# MCU.net
KiCad netlist of a schematic drawn in Altium Designer
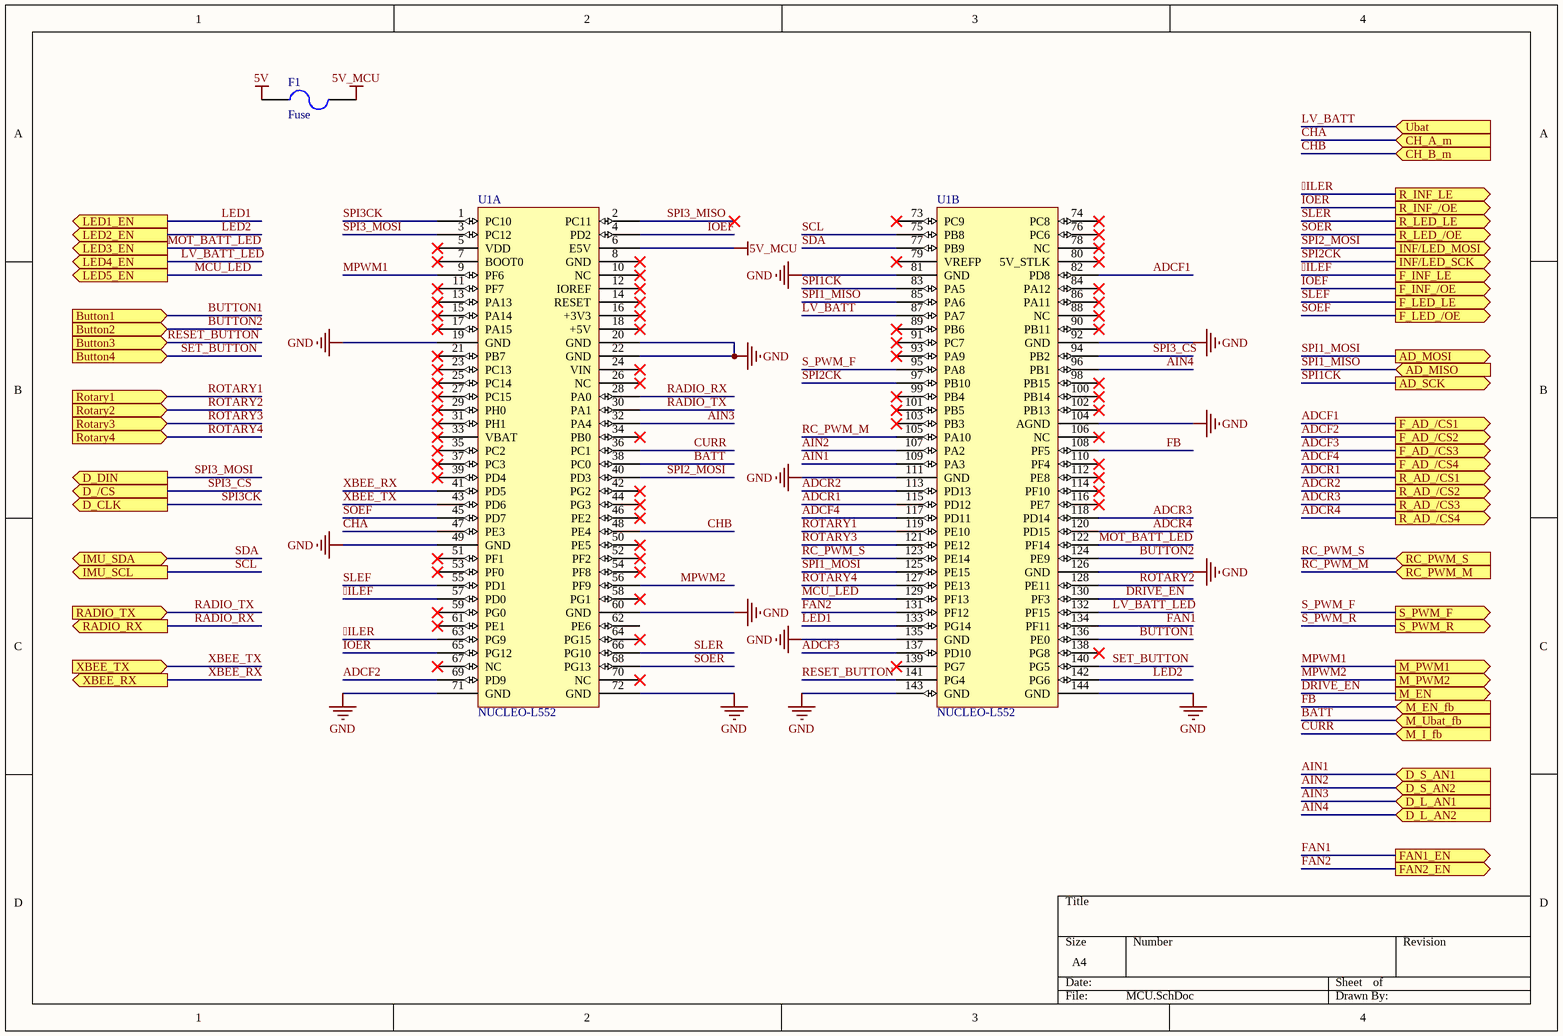
[diagram p0: MCU.SchDoc]

(export (version "E")
  (design (tool "Eeschema 10.0.6"))
  (components
    (comp (ref "F1")
      (value "Fuse")
      (footprint "F_0603")
      (fields (field (name "PART NUMBER") "MC06CF.500") (field (name "NI PART NUMBER") "766324-01"))
      (libsource (lib "Components") (part "Fuse"))
    )
    (comp (ref "U1")
      (value "NUCLEO-L552")
      (footprint "FP_NUCLEO-144")
      (libsource (lib "hallglib") (part "NUCLEO-L552"))
    )
  )
  (nets
    (net (code "1") (name "/ILEF") (class "Default")
      (node (ref "U1") (pin "57") (pinfunction "PD0_57") (pintype "bidirectional"))
    )
    (net (code "2") (name "/ILER") (class "Default")
      (node (ref "U1") (pin "63") (pinfunction "PG9_63") (pintype "bidirectional"))
    )
    (net (code "3") (name "/ADCF1") (class "Default")
      (node (ref "U1") (pin "82") (pinfunction "PD8_82") (pintype "bidirectional"))
    )
    (net (code "4") (name "/ADCF2") (class "Default")
      (node (ref "U1") (pin "69") (pinfunction "PD9_69") (pintype "bidirectional"))
    )
    (net (code "5") (name "/ADCF3") (class "Default")
      (node (ref "U1") (pin "137") (pinfunction "PD10_137") (pintype "bidirectional"))
    )
    (net (code "6") (name "/ADCF4") (class "Default")
      (node (ref "U1") (pin "117") (pinfunction "PD11_117") (pintype "bidirectional"))
    )
    (net (code "7") (name "/ADCR1") (class "Default")
      (node (ref "U1") (pin "115") (pinfunction "PD12_115") (pintype "bidirectional"))
    )
    (net (code "8") (name "/ADCR2") (class "Default")
      (node (ref "U1") (pin "113") (pinfunction "PD13_113") (pintype "bidirectional"))
    )
    (net (code "9") (name "/ADCR3") (class "Default")
      (node (ref "U1") (pin "118") (pinfunction "PD14_118") (pintype "bidirectional"))
    )
    (net (code "10") (name "/ADCR4") (class "Default")
      (node (ref "U1") (pin "120") (pinfunction "PD15_120") (pintype "bidirectional"))
    )
    (net (code "11") (name "/AIN1") (class "Default")
      (node (ref "U1") (pin "109") (pinfunction "PA3_109") (pintype "bidirectional"))
    )
    (net (code "12") (name "/AIN2") (class "Default")
      (node (ref "U1") (pin "107") (pinfunction "PA2_107") (pintype "bidirectional"))
    )
    (net (code "13") (name "/AIN3") (class "Default")
      (node (ref "U1") (pin "32") (pinfunction "PA4_32") (pintype "bidirectional"))
    )
    (net (code "14") (name "/AIN4") (class "Default")
      (node (ref "U1") (pin "96") (pinfunction "PB1_96") (pintype "bidirectional"))
    )
    (net (code "15") (name "/BATT") (class "Default")
      (node (ref "U1") (pin "38") (pinfunction "PC0_38") (pintype "bidirectional"))
    )
    (net (code "16") (name "/BUTTON1") (class "Default")
      (node (ref "U1") (pin "136") (pinfunction "PE0_136") (pintype "bidirectional"))
    )
    (net (code "17") (name "/BUTTON2") (class "Default")
      (node (ref "U1") (pin "124") (pinfunction "PE9_124") (pintype "bidirectional"))
    )
    (net (code "18") (name "/CHA") (class "Default")
      (node (ref "U1") (pin "47") (pinfunction "PE3_47") (pintype "bidirectional"))
    )
    (net (code "19") (name "/CHB") (class "Default")
      (node (ref "U1") (pin "48") (pinfunction "PE4_48") (pintype "bidirectional"))
    )
    (net (code "20") (name "/CURR") (class "Default")
      (node (ref "U1") (pin "36") (pinfunction "PC1_36") (pintype "bidirectional"))
    )
    (net (code "21") (name "/DRIVE_EN") (class "Default")
      (node (ref "U1") (pin "130") (pinfunction "PF3_130") (pintype "bidirectional"))
    )
    (net (code "22") (name "/FAN1") (class "Default")
      (node (ref "U1") (pin "134") (pinfunction "PF11_134") (pintype "bidirectional"))
    )
    (net (code "23") (name "/FAN2") (class "Default")
      (node (ref "U1") (pin "131") (pinfunction "PF12_131") (pintype "bidirectional"))
    )
    (net (code "24") (name "/FB") (class "Default")
      (node (ref "U1") (pin "108") (pinfunction "PF5_108") (pintype "bidirectional"))
    )
    (net (code "25") (name "/IOEF") (class "Default")
      (node (ref "U1") (pin "4") (pinfunction "PD2_4") (pintype "bidirectional"))
    )
    (net (code "26") (name "/IOER") (class "Default")
      (node (ref "U1") (pin "65") (pinfunction "PG12_65") (pintype "bidirectional"))
    )
    (net (code "27") (name "/LED1") (class "Default")
      (node (ref "U1") (pin "133") (pinfunction "PG14_133") (pintype "bidirectional"))
    )
    (net (code "28") (name "/LED2") (class "Default")
      (node (ref "U1") (pin "142") (pinfunction "PG6_142") (pintype "bidirectional"))
    )
    (net (code "29") (name "/LV_BATT") (class "Default")
      (node (ref "U1") (pin "87") (pinfunction "PA7_87") (pintype "bidirectional"))
    )
    (net (code "30") (name "/LV_BATT_LED") (class "Default")
      (node (ref "U1") (pin "132") (pinfunction "PF15_132") (pintype "bidirectional"))
    )
    (net (code "31") (name "/MCU_LED") (class "Default")
      (node (ref "U1") (pin "129") (pinfunction "PF13_129") (pintype "bidirectional"))
    )
    (net (code "32") (name "/MOT_BATT_LED") (class "Default")
      (node (ref "U1") (pin "122") (pinfunction "PF14_122") (pintype "bidirectional"))
    )
    (net (code "33") (name "/MPWM1") (class "Default")
      (node (ref "U1") (pin "9") (pinfunction "PF6_9") (pintype "bidirectional"))
    )
    (net (code "34") (name "/MPWM2") (class "Default")
      (node (ref "U1") (pin "56") (pinfunction "PF9_56") (pintype "bidirectional"))
    )
    (net (code "35") (name "/RADIO_RX") (class "Default")
      (node (ref "U1") (pin "28") (pinfunction "PA0_28") (pintype "bidirectional"))
    )
    (net (code "36") (name "/RADIO_TX") (class "Default")
      (node (ref "U1") (pin "30") (pinfunction "PA1_30") (pintype "bidirectional"))
    )
    (net (code "37") (name "/RC_PWM_M") (class "Default")
      (node (ref "U1") (pin "105") (pinfunction "PA10_105") (pintype "bidirectional"))
    )
    (net (code "38") (name "/RC_PWM_S") (class "Default")
      (node (ref "U1") (pin "123") (pinfunction "PE14_123") (pintype "bidirectional"))
    )
    (net (code "39") (name "/RESET_BUTTON") (class "Default")
      (node (ref "U1") (pin "141") (pinfunction "PG4_141") (pintype "power_in"))
    )
    (net (code "40") (name "/ROTARY1") (class "Default")
      (node (ref "U1") (pin "119") (pinfunction "PE10_119") (pintype "bidirectional"))
    )
    (net (code "41") (name "/ROTARY2") (class "Default")
      (node (ref "U1") (pin "128") (pinfunction "PE11_128") (pintype "bidirectional"))
    )
    (net (code "42") (name "/ROTARY3") (class "Default")
      (node (ref "U1") (pin "121") (pinfunction "PE12_121") (pintype "bidirectional"))
    )
    (net (code "43") (name "/ROTARY4") (class "Default")
      (node (ref "U1") (pin "127") (pinfunction "PE13_127") (pintype "bidirectional"))
    )
    (net (code "44") (name "/SCL") (class "Default")
      (node (ref "U1") (pin "75") (pinfunction "PB8_75") (pintype "bidirectional"))
    )
    (net (code "45") (name "/SDA") (class "Default")
      (node (ref "U1") (pin "77") (pinfunction "PB9_77") (pintype "bidirectional"))
    )
    (net (code "46") (name "/SET_BUTTON") (class "Default")
      (node (ref "U1") (pin "140") (pinfunction "PG5_140") (pintype "bidirectional"))
    )
    (net (code "47") (name "/SLEF") (class "Default")
      (node (ref "U1") (pin "55") (pinfunction "PD1_55") (pintype "bidirectional"))
    )
    (net (code "48") (name "/SLER") (class "Default")
      (node (ref "U1") (pin "66") (pinfunction "PG10_66") (pintype "bidirectional"))
    )
    (net (code "49") (name "/SOEF") (class "Default")
      (node (ref "U1") (pin "45") (pinfunction "PD7_45") (pintype "bidirectional"))
    )
    (net (code "50") (name "/SOER") (class "Default")
      (node (ref "U1") (pin "68") (pinfunction "PG13_68") (pintype "bidirectional"))
    )
    (net (code "51") (name "/SPI1CK") (class "Default")
      (node (ref "U1") (pin "83") (pinfunction "PA5_83") (pintype "bidirectional"))
    )
    (net (code "52") (name "/SPI1_MISO") (class "Default")
      (node (ref "U1") (pin "85") (pinfunction "PA6_85") (pintype "bidirectional"))
    )
    (net (code "53") (name "/SPI1_MOSI") (class "Default")
      (node (ref "U1") (pin "125") (pinfunction "PE15_125") (pintype "bidirectional"))
    )
    (net (code "54") (name "/SPI2CK") (class "Default")
      (node (ref "U1") (pin "97") (pinfunction "PB10_97") (pintype "bidirectional"))
    )
    (net (code "55") (name "/SPI2_MOSI") (class "Default")
      (node (ref "U1") (pin "40") (pinfunction "PD3_40") (pintype "bidirectional"))
    )
    (net (code "56") (name "/SPI3CK") (class "Default")
      (node (ref "U1") (pin "1") (pinfunction "PC10_1") (pintype "bidirectional"))
    )
    (net (code "57") (name "/SPI3_CS") (class "Default")
      (node (ref "U1") (pin "94") (pinfunction "PB2_94") (pintype "bidirectional"))
    )
    (net (code "58") (name "/SPI3_MISO") (class "Default")
      (node (ref "U1") (pin "2") (pinfunction "PC11_2") (pintype "bidirectional+no_connect"))
    )
    (net (code "59") (name "/SPI3_MOSI") (class "Default")
      (node (ref "U1") (pin "3") (pinfunction "PC12_3") (pintype "bidirectional"))
    )
    (net (code "60") (name "/S_PWM_F") (class "Default")
      (node (ref "U1") (pin "95") (pinfunction "PA8_95") (pintype "bidirectional"))
    )
    (net (code "62") (name "/XBEE_RX") (class "Default")
      (node (ref "U1") (pin "41") (pinfunction "PD5_41") (pintype "bidirectional"))
    )
    (net (code "63") (name "/XBEE_TX") (class "Default")
      (node (ref "U1") (pin "43") (pinfunction "PD6_43") (pintype "bidirectional"))
    )
    (net (code "64") (name "5V") (class "Default")
      (node (ref "F1") (pin "1") (pinfunction "1_1") (pintype "passive"))
    )
    (net (code "65") (name "5V_MCU") (class "Default")
      (node (ref "F1") (pin "2") (pinfunction "2_2") (pintype "passive"))
      (node (ref "U1") (pin "6") (pinfunction "E5V_6") (pintype "power_in"))
    )
    (net (code "66") (name "GND") (class "Default")
      (node (ref "U1") (pin "104") (pinfunction "AGND_104") (pintype "passive"))
      (node (ref "U1") (pin "111") (pinfunction "GND_111") (pintype "passive"))
      (node (ref "U1") (pin "126") (pinfunction "GND_126") (pintype "passive"))
      (node (ref "U1") (pin "135") (pinfunction "GND_135") (pintype "passive"))
      (node (ref "U1") (pin "143") (pinfunction "GND_143") (pintype "bidirectional"))
      (node (ref "U1") (pin "144") (pinfunction "GND_144") (pintype "passive"))
      (node (ref "U1") (pin "19") (pinfunction "GND_19") (pintype "passive"))
      (node (ref "U1") (pin "20") (pinfunction "GND_20") (pintype "passive"))
      (node (ref "U1") (pin "22") (pinfunction "GND_22") (pintype "passive"))
      (node (ref "U1") (pin "49") (pinfunction "GND_49") (pintype "passive"))
      (node (ref "U1") (pin "60") (pinfunction "GND_60") (pintype "passive"))
      (node (ref "U1") (pin "71") (pinfunction "GND_71") (pintype "passive"))
      (node (ref "U1") (pin "72") (pinfunction "GND_72") (pintype "passive"))
      (node (ref "U1") (pin "81") (pinfunction "GND_81") (pintype "passive"))
      (node (ref "U1") (pin "92") (pinfunction "GND_92") (pintype "passive"))
    )
    (net (code "67") (name "unconnected-(U1A-+3V3-Pad16)") (class "Default")
      (node (ref "U1") (pin "16") (pinfunction "+3V3_16") (pintype "power_in+no_connect"))
    )
    (net (code "68") (name "unconnected-(U1A-+5V-Pad18)") (class "Default")
      (node (ref "U1") (pin "18") (pinfunction "+5V_18") (pintype "power_in+no_connect"))
    )
    (net (code "69") (name "unconnected-(U1A-BOOT0-Pad7)") (class "Default")
      (node (ref "U1") (pin "7") (pinfunction "BOOT0_7") (pintype "passive+no_connect"))
    )
    (net (code "70") (name "unconnected-(U1A-GND-Pad8)") (class "Default")
      (node (ref "U1") (pin "8") (pinfunction "GND_8") (pintype "passive+no_connect"))
    )
    (net (code "71") (name "unconnected-(U1A-IOREF-Pad12)") (class "Default")
      (node (ref "U1") (pin "12") (pinfunction "IOREF_12") (pintype "passive+no_connect"))
    )
    (net (code "72") (name "unconnected-(U1A-NC-Pad10)") (class "Default")
      (node (ref "U1") (pin "10") (pinfunction "NC_10") (pintype "passive+no_connect"))
    )
    (net (code "73") (name "unconnected-(U1A-NC-Pad26)") (class "Default")
      (node (ref "U1") (pin "26") (pinfunction "NC_26") (pintype "passive+no_connect"))
    )
    (net (code "74") (name "unconnected-(U1A-NC-Pad67)") (class "Default")
      (node (ref "U1") (pin "67") (pinfunction "NC_67") (pintype "bidirectional+no_connect"))
    )
    (net (code "75") (name "unconnected-(U1A-NC-Pad70)") (class "Default")
      (node (ref "U1") (pin "70") (pinfunction "NC_70") (pintype "passive+no_connect"))
    )
    (net (code "76") (name "unconnected-(U1A-PA13-Pad13)") (class "Default")
      (node (ref "U1") (pin "13") (pinfunction "PA13_13") (pintype "bidirectional+no_connect"))
    )
    (net (code "77") (name "unconnected-(U1A-PA14-Pad15)") (class "Default")
      (node (ref "U1") (pin "15") (pinfunction "PA14_15") (pintype "bidirectional+no_connect"))
    )
    (net (code "78") (name "unconnected-(U1A-PA15-Pad17)") (class "Default")
      (node (ref "U1") (pin "17") (pinfunction "PA15_17") (pintype "bidirectional+no_connect"))
    )
    (net (code "79") (name "unconnected-(U1A-PB0-Pad34)") (class "Default")
      (node (ref "U1") (pin "34") (pinfunction "PB0_34") (pintype "bidirectional+no_connect"))
    )
    (net (code "80") (name "unconnected-(U1A-PB7-Pad21)") (class "Default")
      (node (ref "U1") (pin "21") (pinfunction "PB7_21") (pintype "bidirectional+no_connect"))
    )
    (net (code "81") (name "unconnected-(U1A-PC2-Pad35)") (class "Default")
      (node (ref "U1") (pin "35") (pinfunction "PC2_35") (pintype "bidirectional+no_connect"))
    )
    (net (code "82") (name "unconnected-(U1A-PC3-Pad37)") (class "Default")
      (node (ref "U1") (pin "37") (pinfunction "PC3_37") (pintype "bidirectional+no_connect"))
    )
    (net (code "83") (name "unconnected-(U1A-PC13-Pad23)") (class "Default")
      (node (ref "U1") (pin "23") (pinfunction "PC13_23") (pintype "bidirectional+no_connect"))
    )
    (net (code "84") (name "unconnected-(U1A-PC14-Pad25)") (class "Default")
      (node (ref "U1") (pin "25") (pinfunction "PC14_25") (pintype "bidirectional+no_connect"))
    )
    (net (code "85") (name "unconnected-(U1A-PC15-Pad27)") (class "Default")
      (node (ref "U1") (pin "27") (pinfunction "PC15_27") (pintype "bidirectional+no_connect"))
    )
    (net (code "86") (name "unconnected-(U1A-PD4-Pad39)") (class "Default")
      (node (ref "U1") (pin "39") (pinfunction "PD4_39") (pintype "bidirectional+no_connect"))
    )
    (net (code "87") (name "unconnected-(U1A-PE1-Pad61)") (class "Default")
      (node (ref "U1") (pin "61") (pinfunction "PE1_61") (pintype "bidirectional+no_connect"))
    )
    (net (code "88") (name "unconnected-(U1A-PE2-Pad46)") (class "Default")
      (node (ref "U1") (pin "46") (pinfunction "PE2_46") (pintype "bidirectional+no_connect"))
    )
    (net (code "89") (name "unconnected-(U1A-PE5-Pad50)") (class "Default")
      (node (ref "U1") (pin "50") (pinfunction "PE5_50") (pintype "bidirectional+no_connect"))
    )
    (net (code "90") (name "unconnected-(U1A-PE6-Pad62)") (class "Default")
      (node (ref "U1") (pin "62") (pinfunction "PE6_62") (pintype "bidirectional"))
    )
    (net (code "91") (name "unconnected-(U1A-PF0-Pad53)") (class "Default")
      (node (ref "U1") (pin "53") (pinfunction "PF0_53") (pintype "bidirectional+no_connect"))
    )
    (net (code "92") (name "unconnected-(U1A-PF1-Pad51)") (class "Default")
      (node (ref "U1") (pin "51") (pinfunction "PF1_51") (pintype "bidirectional+no_connect"))
    )
    (net (code "93") (name "unconnected-(U1A-PF2-Pad52)") (class "Default")
      (node (ref "U1") (pin "52") (pinfunction "PF2_52") (pintype "bidirectional+no_connect"))
    )
    (net (code "94") (name "unconnected-(U1A-PF7-Pad11)") (class "Default")
      (node (ref "U1") (pin "11") (pinfunction "PF7_11") (pintype "bidirectional+no_connect"))
    )
    (net (code "95") (name "unconnected-(U1A-PF8-Pad54)") (class "Default")
      (node (ref "U1") (pin "54") (pinfunction "PF8_54") (pintype "bidirectional+no_connect"))
    )
    (net (code "96") (name "unconnected-(U1A-PG0-Pad59)") (class "Default")
      (node (ref "U1") (pin "59") (pinfunction "PG0_59") (pintype "bidirectional+no_connect"))
    )
    (net (code "97") (name "unconnected-(U1A-PG1-Pad58)") (class "Default")
      (node (ref "U1") (pin "58") (pinfunction "PG1_58") (pintype "bidirectional+no_connect"))
    )
    (net (code "98") (name "unconnected-(U1A-PG2-Pad42)") (class "Default")
      (node (ref "U1") (pin "42") (pinfunction "PG2_42") (pintype "bidirectional+no_connect"))
    )
    (net (code "99") (name "unconnected-(U1A-PG3-Pad44)") (class "Default")
      (node (ref "U1") (pin "44") (pinfunction "PG3_44") (pintype "bidirectional+no_connect"))
    )
    (net (code "100") (name "unconnected-(U1A-PG15-Pad64)") (class "Default")
      (node (ref "U1") (pin "64") (pinfunction "PG15_64") (pintype "bidirectional+no_connect"))
    )
    (net (code "101") (name "unconnected-(U1A-PH0-Pad29)") (class "Default")
      (node (ref "U1") (pin "29") (pinfunction "PH0_29") (pintype "bidirectional+no_connect"))
    )
    (net (code "102") (name "unconnected-(U1A-PH1-Pad31)") (class "Default")
      (node (ref "U1") (pin "31") (pinfunction "PH1_31") (pintype "bidirectional+no_connect"))
    )
    (net (code "103") (name "unconnected-(U1A-RESET-Pad14)") (class "Default")
      (node (ref "U1") (pin "14") (pinfunction "RESET_14") (pintype "passive+no_connect"))
    )
    (net (code "104") (name "unconnected-(U1A-VBAT-Pad33)") (class "Default")
      (node (ref "U1") (pin "33") (pinfunction "VBAT_33") (pintype "power_in+no_connect"))
    )
    (net (code "105") (name "unconnected-(U1A-VDD-Pad5)") (class "Default")
      (node (ref "U1") (pin "5") (pinfunction "VDD_5") (pintype "power_in+no_connect"))
    )
    (net (code "106") (name "unconnected-(U1A-VIN-Pad24)") (class "Default")
      (node (ref "U1") (pin "24") (pinfunction "VIN_24") (pintype "power_in+no_connect"))
    )
    (net (code "107") (name "unconnected-(U1B-5V_STLK-Pad80)") (class "Default")
      (node (ref "U1") (pin "80") (pinfunction "5V_STLK_80") (pintype "power_in+no_connect"))
    )
    (net (code "108") (name "unconnected-(U1B-NC-Pad78)") (class "Default")
      (node (ref "U1") (pin "78") (pinfunction "NC_78") (pintype "passive+no_connect"))
    )
    (net (code "109") (name "unconnected-(U1B-NC-Pad88)") (class "Default")
      (node (ref "U1") (pin "88") (pinfunction "NC_88") (pintype "passive+no_connect"))
    )
    (net (code "110") (name "unconnected-(U1B-NC-Pad106)") (class "Default")
      (node (ref "U1") (pin "106") (pinfunction "NC_106") (pintype "passive+no_connect"))
    )
    (net (code "111") (name "unconnected-(U1B-PA9-Pad93)") (class "Default")
      (node (ref "U1") (pin "93") (pinfunction "PA9_93") (pintype "bidirectional+no_connect"))
    )
    (net (code "112") (name "unconnected-(U1B-PA11-Pad86)") (class "Default")
      (node (ref "U1") (pin "86") (pinfunction "PA11_86") (pintype "bidirectional+no_connect"))
    )
    (net (code "113") (name "unconnected-(U1B-PA12-Pad84)") (class "Default")
      (node (ref "U1") (pin "84") (pinfunction "PA12_84") (pintype "bidirectional+no_connect"))
    )
    (net (code "114") (name "unconnected-(U1B-PB3-Pad103)") (class "Default")
      (node (ref "U1") (pin "103") (pinfunction "PB3_103") (pintype "bidirectional+no_connect"))
    )
    (net (code "115") (name "unconnected-(U1B-PB4-Pad99)") (class "Default")
      (node (ref "U1") (pin "99") (pinfunction "PB4_99") (pintype "bidirectional+no_connect"))
    )
    (net (code "116") (name "unconnected-(U1B-PB5-Pad101)") (class "Default")
      (node (ref "U1") (pin "101") (pinfunction "PB5_101") (pintype "bidirectional+no_connect"))
    )
    (net (code "117") (name "unconnected-(U1B-PB6-Pad89)") (class "Default")
      (node (ref "U1") (pin "89") (pinfunction "PB6_89") (pintype "bidirectional+no_connect"))
    )
    (net (code "118") (name "unconnected-(U1B-PB11-Pad90)") (class "Default")
      (node (ref "U1") (pin "90") (pinfunction "PB11_90") (pintype "bidirectional+no_connect"))
    )
    (net (code "119") (name "unconnected-(U1B-PB13-Pad102)") (class "Default")
      (node (ref "U1") (pin "102") (pinfunction "PB13_102") (pintype "bidirectional+no_connect"))
    )
    (net (code "120") (name "unconnected-(U1B-PB14-Pad100)") (class "Default")
      (node (ref "U1") (pin "100") (pinfunction "PB14_100") (pintype "bidirectional+no_connect"))
    )
    (net (code "121") (name "unconnected-(U1B-PB15-Pad98)") (class "Default")
      (node (ref "U1") (pin "98") (pinfunction "PB15_98") (pintype "bidirectional+no_connect"))
    )
    (net (code "122") (name "unconnected-(U1B-PC6-Pad76)") (class "Default")
      (node (ref "U1") (pin "76") (pinfunction "PC6_76") (pintype "bidirectional+no_connect"))
    )
    (net (code "123") (name "unconnected-(U1B-PC7-Pad91)") (class "Default")
      (node (ref "U1") (pin "91") (pinfunction "PC7_91") (pintype "bidirectional+no_connect"))
    )
    (net (code "124") (name "unconnected-(U1B-PC8-Pad74)") (class "Default")
      (node (ref "U1") (pin "74") (pinfunction "PC8_74") (pintype "bidirectional+no_connect"))
    )
    (net (code "125") (name "unconnected-(U1B-PC9-Pad73)") (class "Default")
      (node (ref "U1") (pin "73") (pinfunction "PC9_73") (pintype "bidirectional+no_connect"))
    )
    (net (code "126") (name "unconnected-(U1B-PE7-Pad116)") (class "Default")
      (node (ref "U1") (pin "116") (pinfunction "PE7_116") (pintype "bidirectional+no_connect"))
    )
    (net (code "127") (name "unconnected-(U1B-PE8-Pad112)") (class "Default")
      (node (ref "U1") (pin "112") (pinfunction "PE8_112") (pintype "bidirectional+no_connect"))
    )
    (net (code "128") (name "unconnected-(U1B-PF4-Pad110)") (class "Default")
      (node (ref "U1") (pin "110") (pinfunction "PF4_110") (pintype "bidirectional+no_connect"))
    )
    (net (code "129") (name "unconnected-(U1B-PF10-Pad114)") (class "Default")
      (node (ref "U1") (pin "114") (pinfunction "PF10_114") (pintype "bidirectional+no_connect"))
    )
    (net (code "130") (name "unconnected-(U1B-PG7-Pad139)") (class "Default")
      (node (ref "U1") (pin "139") (pinfunction "PG7_139") (pintype "passive+no_connect"))
    )
    (net (code "131") (name "unconnected-(U1B-PG8-Pad138)") (class "Default")
      (node (ref "U1") (pin "138") (pinfunction "PG8_138") (pintype "bidirectional+no_connect"))
    )
    (net (code "132") (name "unconnected-(U1B-VREFP-Pad79)") (class "Default")
      (node (ref "U1") (pin "79") (pinfunction "VREFP_79") (pintype "power_in+no_connect"))
    )
  )
)
